# NQSMHS-SMD.net
KiCad netlist of a schematic drawn in EAGLE
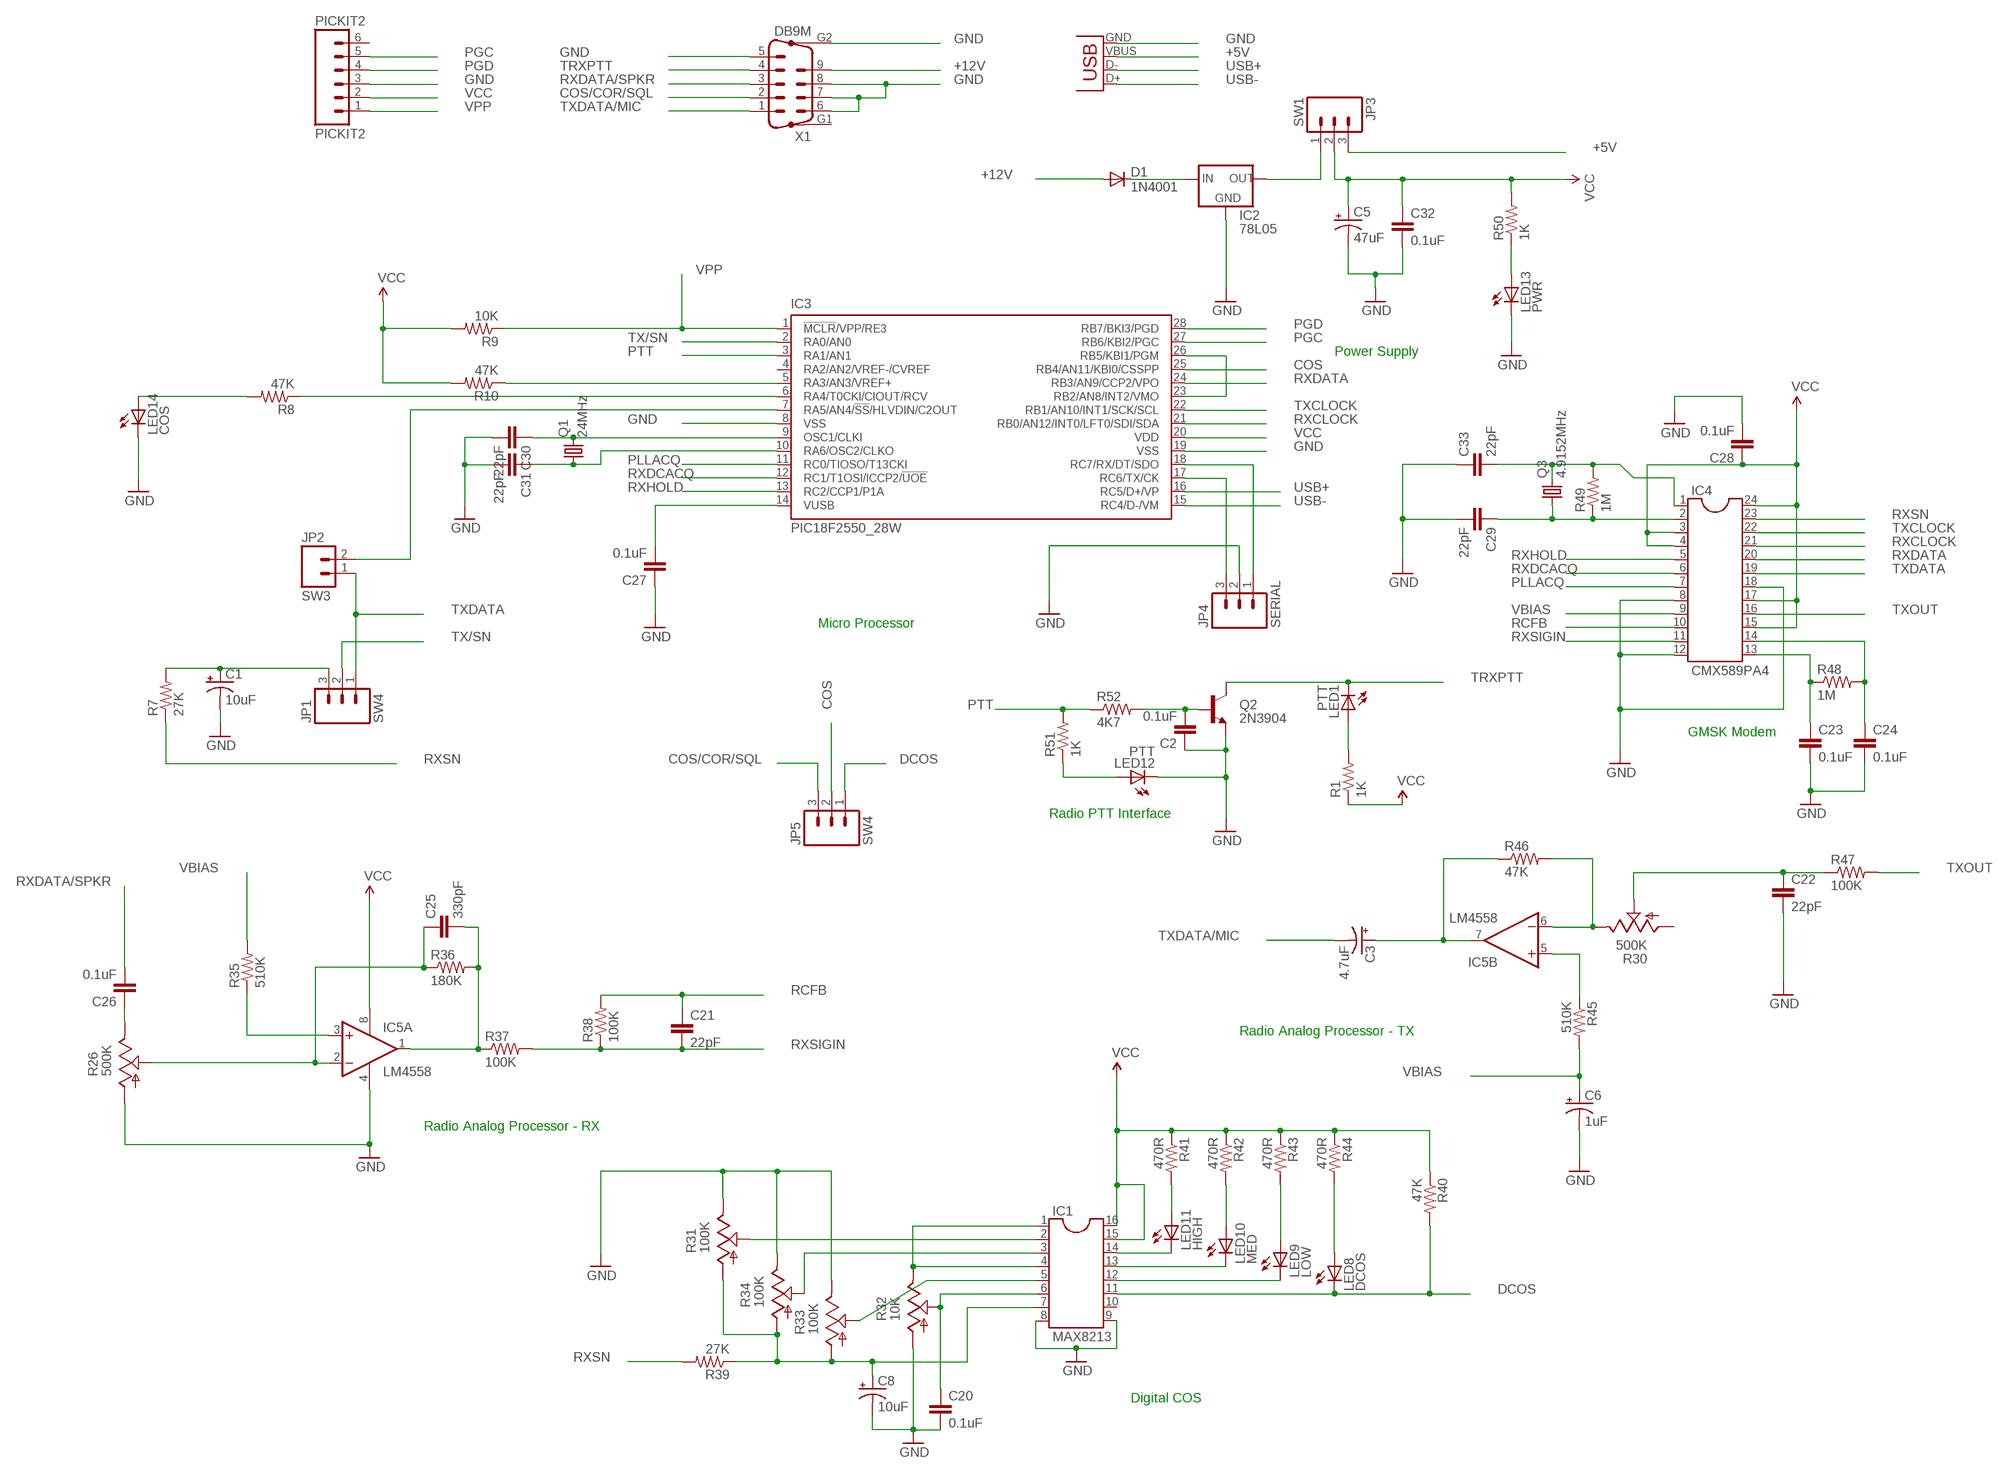
[diagram p0: schematic, sheet 1]

(export (version "E")
  (design (tool "Eeschema 10.0.6"))
  (components
    (comp (ref "C1")
      (value "10uF")
      (footprint "eagle-import:CPOL-RADIAL-100UF-25V")
      (libsource (lib "eagle-import") (part "CAP_POLPTH1"))
    )
    (comp (ref "C2")
      (value "0.1uF")
      (footprint "eagle-import:C0805")
      (libsource (lib "eagle-import") (part "C-EUC0805"))
    )
    (comp (ref "C3")
      (value "4.7uF")
      (footprint "eagle-import:CPOL-RADIAL-10UF-25V")
      (libsource (lib "eagle-import") (part "CAP_POLPTH2"))
    )
    (comp (ref "C5")
      (value "47uF")
      (footprint "eagle-import:CPOL-RADIAL-10UF-25V")
      (libsource (lib "eagle-import") (part "CAP_POLPTH2"))
    )
    (comp (ref "C6")
      (value "1uF")
      (footprint "eagle-import:CPOL-RADIAL-10UF-25V")
      (libsource (lib "eagle-import") (part "CAP_POLPTH2"))
    )
    (comp (ref "C8")
      (value "10uF")
      (footprint "eagle-import:CPOL-RADIAL-10UF-25V")
      (libsource (lib "eagle-import") (part "CAP_POLPTH2"))
    )
    (comp (ref "C20")
      (value "0.1uF")
      (footprint "eagle-import:C0805")
      (libsource (lib "eagle-import") (part "C-EUC0805"))
    )
    (comp (ref "C21")
      (value "22pF")
      (footprint "eagle-import:C0805")
      (libsource (lib "eagle-import") (part "C-EUC0805"))
    )
    (comp (ref "C22")
      (value "22pF")
      (footprint "eagle-import:C0805")
      (libsource (lib "eagle-import") (part "C-EUC0805"))
    )
    (comp (ref "C23")
      (value "0.1uF")
      (footprint "eagle-import:C0805")
      (libsource (lib "eagle-import") (part "C-EUC0805"))
    )
    (comp (ref "C24")
      (value "0.1uF")
      (footprint "eagle-import:C0805")
      (libsource (lib "eagle-import") (part "C-EUC0805"))
    )
    (comp (ref "C25")
      (value "330pF")
      (footprint "eagle-import:C0805")
      (libsource (lib "eagle-import") (part "C-EUC0805"))
    )
    (comp (ref "C26")
      (value "0.1uF")
      (footprint "eagle-import:C0805")
      (libsource (lib "eagle-import") (part "C-EUC0805"))
    )
    (comp (ref "C27")
      (value "0.1uF")
      (footprint "eagle-import:C0805")
      (libsource (lib "eagle-import") (part "C-EUC0805"))
    )
    (comp (ref "C28")
      (value "0.1uF")
      (footprint "eagle-import:C0805")
      (libsource (lib "eagle-import") (part "C-EUC0805"))
    )
    (comp (ref "C29")
      (value "22pF")
      (footprint "eagle-import:C0805")
      (libsource (lib "eagle-import") (part "C-EUC0805"))
    )
    (comp (ref "C30")
      (value "22pF")
      (footprint "eagle-import:C0805")
      (libsource (lib "eagle-import") (part "C-EUC0805"))
    )
    (comp (ref "C31")
      (value "22pF")
      (footprint "eagle-import:C0805")
      (libsource (lib "eagle-import") (part "C-EUC0805"))
    )
    (comp (ref "C32")
      (value "0.1uF")
      (footprint "eagle-import:C0805")
      (libsource (lib "eagle-import") (part "C-EUC0805"))
    )
    (comp (ref "C33")
      (value "22pF")
      (footprint "eagle-import:C0805")
      (libsource (lib "eagle-import") (part "C-EUC0805"))
    )
    (comp (ref "D1")
      (value "1N4001")
      (footprint "eagle-import:SOT23-3")
      (libsource (lib "eagle-import") (part "DIODESOT23"))
    )
    (comp (ref "IC1")
      (value "MAX8213")
      (footprint "eagle-import:DIL16")
      (libsource (lib "eagle-import") (part "DIL16"))
    )
    (comp (ref "IC2")
      (value "78L05")
      (footprint "eagle-import:78LXX")
      (libsource (lib "eagle-import") (part "78LXX"))
    )
    (comp (ref "IC3")
      (value "PIC18F2550_28W")
      (footprint "eagle-import:SO28W")
      (libsource (lib "eagle-import") (part "PIC18F2_28W550"))
    )
    (comp (ref "IC4")
      (value "CMX589PA4")
      (footprint "eagle-import:DIL24-6")
      (libsource (lib "eagle-import") (part "DIL24-6"))
    )
    (comp (ref "IC5")
      (value "LM4558")
      (footprint "eagle-import:SO08")
      (libsource (lib "eagle-import") (part "OPA2U344"))
    )
    (comp (ref "J1")
      (value "USBSMD")
      (footprint "eagle-import:USB-MINIB")
      (libsource (lib "eagle-import") (part "USBSMD"))
    )
    (comp (ref "JP1")
      (value "SW4")
      (footprint "eagle-import:1X03")
      (libsource (lib "eagle-import") (part "M03PTH"))
    )
    (comp (ref "JP2")
      (value "SW3")
      (footprint "eagle-import:1X02")
      (libsource (lib "eagle-import") (part "M02PTH"))
    )
    (comp (ref "JP3")
      (value "SW1")
      (footprint "eagle-import:1X03")
      (libsource (lib "eagle-import") (part "M03PTH"))
    )
    (comp (ref "JP4")
      (value "SERIAL")
      (footprint "eagle-import:1X03")
      (libsource (lib "eagle-import") (part "M03PTH"))
    )
    (comp (ref "JP5")
      (value "SW4")
      (footprint "eagle-import:1X03")
      (libsource (lib "eagle-import") (part "M03PTH"))
    )
    (comp (ref "LED1")
      (value "PTT")
      (footprint "eagle-import:CHIP-LED0805")
      (libsource (lib "eagle-import") (part "LEDCHIP-LED0805"))
    )
    (comp (ref "LED8")
      (value "DCOS")
      (footprint "eagle-import:CHIP-LED0805")
      (libsource (lib "eagle-import") (part "LEDCHIP-LED0805"))
    )
    (comp (ref "LED9")
      (value "LOW")
      (footprint "eagle-import:CHIP-LED0805")
      (libsource (lib "eagle-import") (part "LEDCHIP-LED0805"))
    )
    (comp (ref "LED10")
      (value "MED")
      (footprint "eagle-import:CHIP-LED0805")
      (libsource (lib "eagle-import") (part "LEDCHIP-LED0805"))
    )
    (comp (ref "LED11")
      (value "HIGH")
      (footprint "eagle-import:CHIP-LED0805")
      (libsource (lib "eagle-import") (part "LEDCHIP-LED0805"))
    )
    (comp (ref "LED12")
      (value "PTT")
      (footprint "eagle-import:CHIP-LED0805")
      (libsource (lib "eagle-import") (part "LEDCHIP-LED0805"))
    )
    (comp (ref "LED13")
      (value "PWR")
      (footprint "eagle-import:CHIP-LED0805")
      (libsource (lib "eagle-import") (part "LEDCHIP-LED0805"))
    )
    (comp (ref "LED14")
      (value "COS")
      (footprint "eagle-import:CHIP-LED0805")
      (libsource (lib "eagle-import") (part "LEDCHIP-LED0805"))
    )
    (comp (ref "PICKIT2")
      (value "PICKIT2")
      (footprint "eagle-import:1X06")
      (libsource (lib "eagle-import") (part "M06SIP"))
    )
    (comp (ref "Q1")
      (value "24MHz")
      (footprint "eagle-import:CRYSTAL-SMD-10.5X4.8-2PIN")
      (libsource (lib "eagle-import") (part "CRYSTAL10.5X4.8"))
    )
    (comp (ref "Q2")
      (value "2N3904")
      (footprint "eagle-import:SOT23")
      (libsource (lib "eagle-import") (part "TRANSISTOR_NPNSOT23"))
    )
    (comp (ref "Q3")
      (value "4.9152MHz")
      (footprint "eagle-import:CRYSTAL-SMD-10.5X4.8-2PIN")
      (libsource (lib "eagle-import") (part "CRYSTAL10.5X4.8"))
    )
    (comp (ref "R1")
      (value "1K")
      (footprint "eagle-import:R0805")
      (libsource (lib "eagle-import") (part "R-US_R0805"))
    )
    (comp (ref "R7")
      (value "27K")
      (footprint "eagle-import:R0805")
      (libsource (lib "eagle-import") (part "R-US_R0805"))
    )
    (comp (ref "R8")
      (value "47K")
      (footprint "eagle-import:R0805")
      (libsource (lib "eagle-import") (part "R-US_R0805"))
    )
    (comp (ref "R9")
      (value "10K")
      (footprint "eagle-import:R0805")
      (libsource (lib "eagle-import") (part "R-US_R0805"))
    )
    (comp (ref "R10")
      (value "47K")
      (footprint "eagle-import:R0805")
      (libsource (lib "eagle-import") (part "R-US_R0805"))
    )
    (comp (ref "R26")
      (value "500K")
      (footprint "eagle-import:CA6V")
      (libsource (lib "eagle-import") (part "TRIM_US-CA6V"))
    )
    (comp (ref "R30")
      (value "500K")
      (footprint "eagle-import:CA6V")
      (libsource (lib "eagle-import") (part "TRIM_US-CA6V"))
    )
    (comp (ref "R31")
      (value "100K")
      (footprint "eagle-import:CA6V")
      (libsource (lib "eagle-import") (part "TRIM_US-CA6V"))
    )
    (comp (ref "R32")
      (value "10K")
      (footprint "eagle-import:CA6V")
      (libsource (lib "eagle-import") (part "TRIM_US-CA6V"))
    )
    (comp (ref "R33")
      (value "100K")
      (footprint "eagle-import:CA6V")
      (libsource (lib "eagle-import") (part "TRIM_US-CA6V"))
    )
    (comp (ref "R34")
      (value "100K")
      (footprint "eagle-import:CA6V")
      (libsource (lib "eagle-import") (part "TRIM_US-CA6V"))
    )
    (comp (ref "R35")
      (value "510K")
      (footprint "eagle-import:R0805")
      (libsource (lib "eagle-import") (part "R-US_R0805"))
    )
    (comp (ref "R36")
      (value "180K")
      (footprint "eagle-import:R0805")
      (libsource (lib "eagle-import") (part "R-US_R0805"))
    )
    (comp (ref "R37")
      (value "100K")
      (footprint "eagle-import:R0805")
      (libsource (lib "eagle-import") (part "R-US_R0805"))
    )
    (comp (ref "R38")
      (value "100K")
      (footprint "eagle-import:R0805")
      (libsource (lib "eagle-import") (part "R-US_R0805"))
    )
    (comp (ref "R39")
      (value "27K")
      (footprint "eagle-import:R0805")
      (libsource (lib "eagle-import") (part "R-US_R0805"))
    )
    (comp (ref "R40")
      (value "47K")
      (footprint "eagle-import:R0805")
      (libsource (lib "eagle-import") (part "R-US_R0805"))
    )
    (comp (ref "R41")
      (value "470R")
      (footprint "eagle-import:R0805")
      (libsource (lib "eagle-import") (part "R-US_R0805"))
    )
    (comp (ref "R42")
      (value "470R")
      (footprint "eagle-import:R0805")
      (libsource (lib "eagle-import") (part "R-US_R0805"))
    )
    (comp (ref "R43")
      (value "470R")
      (footprint "eagle-import:R0805")
      (libsource (lib "eagle-import") (part "R-US_R0805"))
    )
    (comp (ref "R44")
      (value "470R")
      (footprint "eagle-import:R0805")
      (libsource (lib "eagle-import") (part "R-US_R0805"))
    )
    (comp (ref "R45")
      (value "510K")
      (footprint "eagle-import:R0805")
      (libsource (lib "eagle-import") (part "R-US_R0805"))
    )
    (comp (ref "R46")
      (value "47K")
      (footprint "eagle-import:R0805")
      (libsource (lib "eagle-import") (part "R-US_R0805"))
    )
    (comp (ref "R47")
      (value "100K")
      (footprint "eagle-import:R0805")
      (libsource (lib "eagle-import") (part "R-US_R0805"))
    )
    (comp (ref "R48")
      (value "1M")
      (footprint "eagle-import:R0805")
      (libsource (lib "eagle-import") (part "R-US_R0805"))
    )
    (comp (ref "R49")
      (value "1M")
      (footprint "eagle-import:R0805")
      (libsource (lib "eagle-import") (part "R-US_R0805"))
    )
    (comp (ref "R50")
      (value "1K")
      (footprint "eagle-import:R0805")
      (libsource (lib "eagle-import") (part "R-US_R0805"))
    )
    (comp (ref "R51")
      (value "1K")
      (footprint "eagle-import:R0805")
      (libsource (lib "eagle-import") (part "R-US_R0805"))
    )
    (comp (ref "R52")
      (value "4K7")
      (footprint "eagle-import:R0805")
      (libsource (lib "eagle-import") (part "R-US_R0805"))
    )
    (comp (ref "X1")
      (value "DB9M")
      (footprint "eagle-import:M09HP")
      (libsource (lib "eagle-import") (part "M09HP"))
    )
  )
  (nets
    (net (code "1") (name "/+5V") (class "Default")
      (node (ref "J1") (pin "VBUS") (pinfunction "VBUS_VBUS") (pintype "bidirectional"))
      (node (ref "JP3") (pin "3") (pinfunction "3_3") (pintype "passive"))
    )
    (net (code "2") (name "/+12V") (class "Default")
      (node (ref "D1") (pin "1") (pinfunction "A_1") (pintype "passive"))
      (node (ref "X1") (pin "9") (pinfunction "9_9") (pintype "passive"))
    )
    (net (code "3") (name "/COS") (class "Default")
      (node (ref "IC3") (pin "25") (pinfunction "RB4/AN11/KBI0/CSSPP_25") (pintype "bidirectional"))
      (node (ref "JP5") (pin "2") (pinfunction "2_2") (pintype "passive"))
    )
    (net (code "4") (name "/COS{slash}COR{slash}SQL") (class "Default")
      (node (ref "JP5") (pin "3") (pinfunction "3_3") (pintype "passive"))
      (node (ref "X1") (pin "2") (pinfunction "2_2") (pintype "passive"))
    )
    (net (code "5") (name "/DCOS") (class "Default")
      (node (ref "IC1") (pin "11") (pinfunction "11_11") (pintype "passive"))
      (node (ref "JP5") (pin "1") (pinfunction "1_1") (pintype "passive"))
      (node (ref "LED8") (pin "C") (pinfunction "C_C") (pintype "passive"))
      (node (ref "R40") (pin "2") (pinfunction "2_2") (pintype "passive"))
    )
    (net (code "6") (name "/PGC") (class "Default")
      (node (ref "IC3") (pin "27") (pinfunction "RB6/KBI2/PGC_27") (pintype "bidirectional"))
      (node (ref "PICKIT2") (pin "5") (pinfunction "5_5") (pintype "passive"))
    )
    (net (code "7") (name "/PGD") (class "Default")
      (node (ref "IC3") (pin "28") (pinfunction "RB7/BKI3/PGD_28") (pintype "bidirectional"))
      (node (ref "PICKIT2") (pin "4") (pinfunction "4_4") (pintype "passive"))
    )
    (net (code "8") (name "/PLLACQ") (class "Default")
      (node (ref "IC3") (pin "11") (pinfunction "RC0/TIOSO/T13CKI_11") (pintype "bidirectional"))
      (node (ref "IC4") (pin "7") (pinfunction "7_7") (pintype "passive"))
    )
    (net (code "9") (name "/PTT") (class "Default")
      (node (ref "IC3") (pin "3") (pinfunction "RA1/AN1_3") (pintype "bidirectional"))
      (node (ref "R51") (pin "2") (pinfunction "2_2") (pintype "passive"))
      (node (ref "R52") (pin "1") (pinfunction "1_1") (pintype "passive"))
    )
    (net (code "10") (name "/RCFB") (class "Default")
      (node (ref "C21") (pin "1") (pinfunction "1_1") (pintype "passive"))
      (node (ref "IC4") (pin "10") (pinfunction "10_10") (pintype "passive"))
      (node (ref "R38") (pin "2") (pinfunction "2_2") (pintype "passive"))
    )
    (net (code "11") (name "/RXCLOCK") (class "Default")
      (node (ref "IC3") (pin "21") (pinfunction "RB0/AN12/INT0/LFT0/SDI/SDA_21") (pintype "bidirectional"))
      (node (ref "IC4") (pin "21") (pinfunction "21_21") (pintype "passive"))
    )
    (net (code "12") (name "/RXDATA") (class "Default")
      (node (ref "IC3") (pin "24") (pinfunction "RB3/AN9/CCP2/VPO_24") (pintype "bidirectional"))
      (node (ref "IC4") (pin "20") (pinfunction "20_20") (pintype "passive"))
    )
    (net (code "13") (name "/RXDATA{slash}SPKR") (class "Default")
      (node (ref "C26") (pin "2") (pinfunction "2_2") (pintype "passive"))
      (node (ref "X1") (pin "3") (pinfunction "3_3") (pintype "passive"))
    )
    (net (code "14") (name "/RXDCACQ") (class "Default")
      (node (ref "IC3") (pin "12") (pinfunction "RC1/T1OSI/ICCP2/~{UOE}_12") (pintype "bidirectional"))
      (node (ref "IC4") (pin "6") (pinfunction "6_6") (pintype "passive"))
    )
    (net (code "15") (name "/RXHOLD") (class "Default")
      (node (ref "IC3") (pin "13") (pinfunction "RC2/CCP1/P1A_13") (pintype "bidirectional"))
      (node (ref "IC4") (pin "5") (pinfunction "5_5") (pintype "passive"))
    )
    (net (code "16") (name "/RXSIGIN") (class "Default")
      (node (ref "C21") (pin "2") (pinfunction "2_2") (pintype "passive"))
      (node (ref "IC4") (pin "11") (pinfunction "11_11") (pintype "passive"))
      (node (ref "R37") (pin "2") (pinfunction "2_2") (pintype "passive"))
      (node (ref "R38") (pin "1") (pinfunction "1_1") (pintype "passive"))
    )
    (net (code "17") (name "/RXSN") (class "Default")
      (node (ref "IC4") (pin "23") (pinfunction "23_23") (pintype "passive"))
      (node (ref "R39") (pin "2") (pinfunction "2_2") (pintype "passive"))
      (node (ref "R7") (pin "1") (pinfunction "1_1") (pintype "passive"))
    )
    (net (code "18") (name "/TRXPTT") (class "Default")
      (node (ref "LED1") (pin "C") (pinfunction "C_C") (pintype "passive"))
      (node (ref "Q2") (pin "3") (pinfunction "C_3") (pintype "passive"))
      (node (ref "X1") (pin "4") (pinfunction "4_4") (pintype "passive"))
    )
    (net (code "19") (name "/TXCLOCK") (class "Default")
      (node (ref "IC3") (pin "22") (pinfunction "RB1/AN10/INT1/SCK/SCL_22") (pintype "bidirectional"))
      (node (ref "IC4") (pin "22") (pinfunction "22_22") (pintype "passive"))
    )
    (net (code "20") (name "/TXDATA") (class "Default")
      (node (ref "IC4") (pin "19") (pinfunction "19_19") (pintype "passive"))
      (node (ref "JP1") (pin "1") (pinfunction "1_1") (pintype "passive"))
      (node (ref "JP2") (pin "1") (pinfunction "1_1") (pintype "passive"))
    )
    (net (code "21") (name "/TXDATA{slash}MIC") (class "Default")
      (node (ref "C3") (pin "2") (pinfunction "-_2") (pintype "passive"))
      (node (ref "X1") (pin "1") (pinfunction "1_1") (pintype "passive"))
    )
    (net (code "22") (name "/TXOUT") (class "Default")
      (node (ref "IC4") (pin "16") (pinfunction "16_16") (pintype "passive"))
      (node (ref "R47") (pin "2") (pinfunction "2_2") (pintype "passive"))
    )
    (net (code "23") (name "/TX{slash}SN") (class "Default")
      (node (ref "IC3") (pin "2") (pinfunction "RA0/AN0_2") (pintype "bidirectional"))
      (node (ref "JP1") (pin "2") (pinfunction "2_2") (pintype "passive"))
    )
    (net (code "24") (name "/USB+") (class "Default")
      (node (ref "IC3") (pin "16") (pinfunction "RC5/D+/VP_16") (pintype "bidirectional"))
      (node (ref "J1") (pin "D-") (pinfunction "D-_D-") (pintype "bidirectional"))
    )
    (net (code "25") (name "/USB-") (class "Default")
      (node (ref "IC3") (pin "15") (pinfunction "RC4/D-/VM_15") (pintype "bidirectional"))
      (node (ref "J1") (pin "D+") (pinfunction "D+_D+") (pintype "bidirectional"))
    )
    (net (code "26") (name "/VBIAS") (class "Default")
      (node (ref "C6") (pin "1") (pinfunction "+_1") (pintype "passive"))
      (node (ref "IC4") (pin "9") (pinfunction "9_9") (pintype "passive"))
      (node (ref "R35") (pin "2") (pinfunction "2_2") (pintype "passive"))
      (node (ref "R45") (pin "2") (pinfunction "2_2") (pintype "passive"))
    )
    (net (code "27") (name "/VPP") (class "Default")
      (node (ref "IC3") (pin "1") (pinfunction "~{MCLR}/VPP/RE3_1") (pintype "input"))
      (node (ref "PICKIT2") (pin "1") (pinfunction "1_1") (pintype "passive"))
      (node (ref "R9") (pin "1") (pinfunction "1_1") (pintype "passive"))
    )
    (net (code "28") (name "GND") (class "Default")
      (node (ref "C1") (pin "2") (pinfunction "-_2") (pintype "passive"))
      (node (ref "C2") (pin "1") (pinfunction "1_1") (pintype "passive"))
      (node (ref "C20") (pin "2") (pinfunction "2_2") (pintype "passive"))
      (node (ref "C22") (pin "2") (pinfunction "2_2") (pintype "passive"))
      (node (ref "C23") (pin "2") (pinfunction "2_2") (pintype "passive"))
      (node (ref "C24") (pin "2") (pinfunction "2_2") (pintype "passive"))
      (node (ref "C27") (pin "1") (pinfunction "1_1") (pintype "passive"))
      (node (ref "C28") (pin "2") (pinfunction "2_2") (pintype "passive"))
      (node (ref "C29") (pin "2") (pinfunction "2_2") (pintype "passive"))
      (node (ref "C30") (pin "2") (pinfunction "2_2") (pintype "passive"))
      (node (ref "C31") (pin "2") (pinfunction "2_2") (pintype "passive"))
      (node (ref "C32") (pin "2") (pinfunction "2_2") (pintype "passive"))
      (node (ref "C33") (pin "1") (pinfunction "1_1") (pintype "passive"))
      (node (ref "C5") (pin "2") (pinfunction "-_2") (pintype "passive"))
      (node (ref "C6") (pin "2") (pinfunction "-_2") (pintype "passive"))
      (node (ref "C8") (pin "2") (pinfunction "-_2") (pintype "passive"))
      (node (ref "IC1") (pin "8") (pinfunction "8_8") (pintype "passive"))
      (node (ref "IC1") (pin "9") (pinfunction "9_9") (pintype "passive"))
      (node (ref "IC2") (pin "GND") (pinfunction "GND_GND") (pintype "input"))
      (node (ref "IC3") (pin "19") (pinfunction "VSS_19") (pintype "power_in"))
      (node (ref "IC3") (pin "8") (pinfunction "VSS_8") (pintype "power_in"))
      (node (ref "IC4") (pin "12") (pinfunction "12_12") (pintype "passive"))
      (node (ref "IC4") (pin "18") (pinfunction "18_18") (pintype "passive"))
      (node (ref "IC4") (pin "8") (pinfunction "8_8") (pintype "passive"))
      (node (ref "IC5") (pin "4") (pinfunction "V-_4") (pintype "power_in"))
      (node (ref "J1") (pin "GND") (pinfunction "GND_GND") (pintype "bidirectional"))
      (node (ref "JP4") (pin "2") (pinfunction "2_2") (pintype "passive"))
      (node (ref "LED12") (pin "C") (pinfunction "C_C") (pintype "passive"))
      (node (ref "LED13") (pin "C") (pinfunction "C_C") (pintype "passive"))
      (node (ref "LED14") (pin "C") (pinfunction "C_C") (pintype "passive"))
      (node (ref "PICKIT2") (pin "3") (pinfunction "3_3") (pintype "passive"))
      (node (ref "Q2") (pin "2") (pinfunction "E_2") (pintype "passive"))
      (node (ref "R26") (pin "A") (pinfunction "A_A") (pintype "passive"))
      (node (ref "R31") (pin "E") (pinfunction "E_E") (pintype "passive"))
      (node (ref "R32") (pin "A") (pinfunction "A_A") (pintype "passive"))
      (node (ref "R33") (pin "E") (pinfunction "E_E") (pintype "passive"))
      (node (ref "R34") (pin "E") (pinfunction "E_E") (pintype "passive"))
      (node (ref "X1") (pin "5") (pinfunction "5_5") (pintype "passive"))
      (node (ref "X1") (pin "6") (pinfunction "6_6") (pintype "passive"))
      (node (ref "X1") (pin "7") (pinfunction "7_7") (pintype "passive"))
      (node (ref "X1") (pin "8") (pinfunction "8_8") (pintype "passive"))
      (node (ref "X1") (pin "G2") (pinfunction "G2_G2") (pintype "passive"))
    )
    (net (code "29") (name "Net-(C1-+)") (class "Default")
      (node (ref "C1") (pin "1") (pinfunction "+_1") (pintype "passive"))
      (node (ref "JP1") (pin "3") (pinfunction "3_3") (pintype "passive"))
      (node (ref "R7") (pin "2") (pinfunction "2_2") (pintype "passive"))
    )
    (net (code "30") (name "Net-(C3-+)") (class "Default")
      (node (ref "C3") (pin "1") (pinfunction "+_1") (pintype "passive"))
      (node (ref "IC5") (pin "7") (pinfunction "OUT_7") (pintype "output"))
      (node (ref "R46") (pin "1") (pinfunction "1_1") (pintype "passive"))
    )
    (net (code "31") (name "Net-(C8-+)") (class "Default")
      (node (ref "C8") (pin "1") (pinfunction "+_1") (pintype "passive"))
      (node (ref "IC1") (pin "7") (pinfunction "7_7") (pintype "passive"))
      (node (ref "R31") (pin "A") (pinfunction "A_A") (pintype "passive"))
      (node (ref "R33") (pin "A") (pinfunction "A_A") (pintype "passive"))
      (node (ref "R34") (pin "A") (pinfunction "A_A") (pintype "passive"))
      (node (ref "R39") (pin "1") (pinfunction "1_1") (pintype "passive"))
    )
    (net (code "32") (name "Net-(C20-Pad1)") (class "Default")
      (node (ref "C20") (pin "1") (pinfunction "1_1") (pintype "passive"))
      (node (ref "IC1") (pin "6") (pinfunction "6_6") (pintype "passive"))
      (node (ref "R32") (pin "S") (pinfunction "S_S") (pintype "passive"))
    )
    (net (code "33") (name "Net-(C22-Pad1)") (class "Default")
      (node (ref "C22") (pin "1") (pinfunction "1_1") (pintype "passive"))
      (node (ref "R30") (pin "S") (pinfunction "S_S") (pintype "passive"))
      (node (ref "R47") (pin "1") (pinfunction "1_1") (pintype "passive"))
    )
    (net (code "34") (name "Net-(C23-Pad1)") (class "Default")
      (node (ref "C23") (pin "1") (pinfunction "1_1") (pintype "passive"))
      (node (ref "IC4") (pin "13") (pinfunction "13_13") (pintype "passive"))
      (node (ref "R48") (pin "1") (pinfunction "1_1") (pintype "passive"))
    )
    (net (code "35") (name "Net-(C24-Pad1)") (class "Default")
      (node (ref "C24") (pin "1") (pinfunction "1_1") (pintype "passive"))
      (node (ref "IC4") (pin "14") (pinfunction "14_14") (pintype "passive"))
      (node (ref "R48") (pin "2") (pinfunction "2_2") (pintype "passive"))
    )
    (net (code "36") (name "Net-(C26-Pad1)") (class "Default")
      (node (ref "C26") (pin "1") (pinfunction "1_1") (pintype "passive"))
      (node (ref "R26") (pin "E") (pinfunction "E_E") (pintype "passive"))
    )
    (net (code "37") (name "Net-(D1-C)") (class "Default")
      (node (ref "D1") (pin "3") (pinfunction "C_3") (pintype "passive"))
      (node (ref "IC2") (pin "IN") (pinfunction "IN_IN") (pintype "input"))
    )
    (net (code "38") (name "Net-(IC1-Pad1)") (class "Default")
      (node (ref "IC1") (pin "1") (pinfunction "1_1") (pintype "passive"))
      (node (ref "IC1") (pin "4") (pinfunction "4_4") (pintype "passive"))
      (node (ref "R32") (pin "E") (pinfunction "E_E") (pintype "passive"))
    )
    (net (code "39") (name "Net-(IC1-Pad2)") (class "Default")
      (node (ref "IC1") (pin "2") (pinfunction "2_2") (pintype "passive"))
      (node (ref "R31") (pin "S") (pinfunction "S_S") (pintype "passive"))
    )
    (net (code "40") (name "Net-(IC1-Pad3)") (class "Default")
      (node (ref "IC1") (pin "3") (pinfunction "3_3") (pintype "passive"))
      (node (ref "R34") (pin "S") (pinfunction "S_S") (pintype "passive"))
    )
    (net (code "41") (name "Net-(IC1-Pad5)") (class "Default")
      (node (ref "IC1") (pin "5") (pinfunction "5_5") (pintype "passive"))
      (node (ref "R33") (pin "S") (pinfunction "S_S") (pintype "passive"))
    )
    (net (code "42") (name "Net-(IC1-Pad12)") (class "Default")
      (node (ref "IC1") (pin "12") (pinfunction "12_12") (pintype "passive"))
      (node (ref "LED9") (pin "C") (pinfunction "C_C") (pintype "passive"))
    )
    (net (code "43") (name "Net-(IC1-Pad13)") (class "Default")
      (node (ref "IC1") (pin "13") (pinfunction "13_13") (pintype "passive"))
      (node (ref "LED10") (pin "C") (pinfunction "C_C") (pintype "passive"))
    )
    (net (code "44") (name "Net-(IC1-Pad14)") (class "Default")
      (node (ref "IC1") (pin "14") (pinfunction "14_14") (pintype "passive"))
      (node (ref "LED11") (pin "C") (pinfunction "C_C") (pintype "passive"))
    )
    (net (code "45") (name "Net-(IC2-PadOUT)") (class "Default")
      (node (ref "IC2") (pin "OUT") (pinfunction "OUT_OUT") (pintype "passive"))
      (node (ref "JP3") (pin "1") (pinfunction "1_1") (pintype "passive"))
    )
    (net (code "46") (name "Net-(IC3-OSC1{slash}CLKI)") (class "Default")
      (node (ref "C30") (pin "1") (pinfunction "1_1") (pintype "passive"))
      (node (ref "IC3") (pin "9") (pinfunction "OSC1/CLKI_9") (pintype "input"))
      (node (ref "Q1") (pin "P$2") (pinfunction "2_P$2") (pintype "passive"))
    )
    (net (code "47") (name "Net-(IC3-RA3{slash}AN3{slash}VREF+)") (class "Default")
      (node (ref "IC3") (pin "5") (pinfunction "RA3/AN3/VREF+_5") (pintype "bidirectional"))
      (node (ref "R10") (pin "1") (pinfunction "1_1") (pintype "passive"))
    )
    (net (code "48") (name "Net-(IC3-RA4{slash}T0CKI{slash}CIOUT{slash}RCV)") (class "Default")
      (node (ref "IC3") (pin "6") (pinfunction "RA4/T0CKI/CIOUT/RCV_6") (pintype "bidirectional"))
      (node (ref "R8") (pin "1") (pinfunction "1_1") (pintype "passive"))
    )
    (net (code "49") (name "Net-(IC3-RA5{slash}AN4{slash}~{SS}{slash}HLVDIN{slash}C2OUT)") (class "Default")
      (node (ref "IC3") (pin "7") (pinfunction "RA5/AN4/~{SS}/HLVDIN/C2OUT_7") (pintype "bidirectional"))
      (node (ref "JP2") (pin "2") (pinfunction "2_2") (pintype "passive"))
    )
    (net (code "50") (name "Net-(IC3-RA6{slash}OSC2{slash}CLKO)") (class "Default")
      (node (ref "C31") (pin "1") (pinfunction "1_1") (pintype "passive"))
      (node (ref "IC3") (pin "10") (pinfunction "RA6/OSC2/CLKO_10") (pintype "output"))
      (node (ref "Q1") (pin "P$1") (pinfunction "1_P$1") (pintype "passive"))
    )
    (net (code "51") (name "Net-(IC3-RB2{slash}AN8{slash}INT2{slash}VMO)") (class "Default")
      (node (ref "IC3") (pin "23") (pinfunction "RB2/AN8/INT2/VMO_23") (pintype "bidirectional"))
      (node (ref "IC3") (pin "26") (pinfunction "RB5/KBI1/PGM_26") (pintype "bidirectional"))
    )
    (net (code "52") (name "Net-(IC3-RC6{slash}TX{slash}CK)") (class "Default")
      (node (ref "IC3") (pin "17") (pinfunction "RC6/TX/CK_17") (pintype "bidirectional"))
      (node (ref "JP4") (pin "3") (pinfunction "3_3") (pintype "passive"))
    )
    (net (code "53") (name "Net-(IC3-RC7{slash}RX{slash}DT{slash}SDO)") (class "Default")
      (node (ref "IC3") (pin "18") (pinfunction "RC7/RX/DT/SDO_18") (pintype "bidirectional"))
      (node (ref "JP4") (pin "1") (pinfunction "1_1") (pintype "passive"))
    )
    (net (code "54") (name "Net-(IC3-VUSB)") (class "Default")
      (node (ref "C27") (pin "2") (pinfunction "2_2") (pintype "passive"))
      (node (ref "IC3") (pin "14") (pinfunction "VUSB_14") (pintype "bidirectional"))
    )
    (net (code "55") (name "Net-(IC5A-+IN)") (class "Default")
      (node (ref "IC5") (pin "3") (pinfunction "+IN_3") (pintype "input"))
      (node (ref "R35") (pin "1") (pinfunction "1_1") (pintype "passive"))
    )
    (net (code "56") (name "Net-(IC5A--IN)") (class "Default")
      (node (ref "C25") (pin "1") (pinfunction "1_1") (pintype "passive"))
      (node (ref "IC5") (pin "2") (pinfunction "-IN_2") (pintype "input"))
      (node (ref "R26") (pin "S") (pinfunction "S_S") (pintype "passive"))
      (node (ref "R36") (pin "1") (pinfunction "1_1") (pintype "passive"))
    )
    (net (code "57") (name "Net-(IC5A-OUT)") (class "Default")
      (node (ref "C25") (pin "2") (pinfunction "2_2") (pintype "passive"))
      (node (ref "IC5") (pin "1") (pinfunction "OUT_1") (pintype "output"))
      (node (ref "R36") (pin "2") (pinfunction "2_2") (pintype "passive"))
      (node (ref "R37") (pin "1") (pinfunction "1_1") (pintype "passive"))
    )
    (net (code "58") (name "Net-(IC5B-+IN)") (class "Default")
      (node (ref "IC5") (pin "5") (pinfunction "+IN_5") (pintype "input"))
      (node (ref "R45") (pin "1") (pinfunction "1_1") (pintype "passive"))
    )
    (net (code "59") (name "Net-(IC5B--IN)") (class "Default")
      (node (ref "IC5") (pin "6") (pinfunction "-IN_6") (pintype "input"))
      (node (ref "R30") (pin "E") (pinfunction "E_E") (pintype "passive"))
      (node (ref "R46") (pin "2") (pinfunction "2_2") (pintype "passive"))
    )
    (net (code "60") (name "Net-(LED1-PadA)") (class "Default")
      (node (ref "LED1") (pin "A") (pinfunction "A_A") (pintype "passive"))
      (node (ref "R1") (pin "2") (pinfunction "2_2") (pintype "passive"))
    )
    (net (code "61") (name "Net-(LED8-PadA)") (class "Default")
      (node (ref "LED8") (pin "A") (pinfunction "A_A") (pintype "passive"))
      (node (ref "R44") (pin "2") (pinfunction "2_2") (pintype "passive"))
    )
    (net (code "62") (name "Net-(LED9-PadA)") (class "Default")
      (node (ref "LED9") (pin "A") (pinfunction "A_A") (pintype "passive"))
      (node (ref "R43") (pin "2") (pinfunction "2_2") (pintype "passive"))
    )
    (net (code "63") (name "Net-(LED10-PadA)") (class "Default")
      (node (ref "LED10") (pin "A") (pinfunction "A_A") (pintype "passive"))
      (node (ref "R42") (pin "2") (pinfunction "2_2") (pintype "passive"))
    )
    (net (code "64") (name "Net-(LED11-PadA)") (class "Default")
      (node (ref "LED11") (pin "A") (pinfunction "A_A") (pintype "passive"))
      (node (ref "R41") (pin "2") (pinfunction "2_2") (pintype "passive"))
    )
    (net (code "65") (name "Net-(LED12-PadA)") (class "Default")
      (node (ref "LED12") (pin "A") (pinfunction "A_A") (pintype "passive"))
      (node (ref "R51") (pin "1") (pinfunction "1_1") (pintype "passive"))
    )
    (net (code "66") (name "Net-(LED13-PadA)") (class "Default")
      (node (ref "LED13") (pin "A") (pinfunction "A_A") (pintype "passive"))
      (node (ref "R50") (pin "1") (pinfunction "1_1") (pintype "passive"))
    )
    (net (code "67") (name "Net-(LED14-PadA)") (class "Default")
      (node (ref "LED14") (pin "A") (pinfunction "A_A") (pintype "passive"))
      (node (ref "R8") (pin "2") (pinfunction "2_2") (pintype "passive"))
    )
    (net (code "68") (name "Net-(Q2-B)") (class "Default")
      (node (ref "C2") (pin "2") (pinfunction "2_2") (pintype "passive"))
      (node (ref "Q2") (pin "1") (pinfunction "B_1") (pintype "passive"))
      (node (ref "R52") (pin "2") (pinfunction "2_2") (pintype "passive"))
    )
    (net (code "69") (name "Net-(Q3-1)") (class "Default")
      (node (ref "C29") (pin "1") (pinfunction "1_1") (pintype "passive"))
      (node (ref "IC4") (pin "2") (pinfunction "2_2") (pintype "passive"))
      (node (ref "Q3") (pin "P$1") (pinfunction "1_P$1") (pintype "passive"))
      (node (ref "R49") (pin "1") (pinfunction "1_1") (pintype "passive"))
    )
    (net (code "70") (name "Net-(Q3-2)") (class "Default")
      (node (ref "C33") (pin "2") (pinfunction "2_2") (pintype "passive"))
      (node (ref "IC4") (pin "1") (pinfunction "1_1") (pintype "passive"))
      (node (ref "Q3") (pin "P$2") (pinfunction "2_P$2") (pintype "passive"))
      (node (ref "R49") (pin "2") (pinfunction "2_2") (pintype "passive"))
    )
    (net (code "71") (name "VCC") (class "Default")
      (node (ref "C28") (pin "1") (pinfunction "1_1") (pintype "passive"))
      (node (ref "C32") (pin "1") (pinfunction "1_1") (pintype "passive"))
      (node (ref "C5") (pin "1") (pinfunction "+_1") (pintype "passive"))
      (node (ref "IC1") (pin "15") (pinfunction "15_15") (pintype "passive"))
      (node (ref "IC1") (pin "16") (pinfunction "16_16") (pintype "passive"))
      (node (ref "IC3") (pin "20") (pinfunction "VDD_20") (pintype "power_in"))
      (node (ref "IC4") (pin "15") (pinfunction "15_15") (pintype "passive"))
      (node (ref "IC4") (pin "17") (pinfunction "17_17") (pintype "passive"))
      (node (ref "IC4") (pin "24") (pinfunction "24_24") (pintype "passive"))
      (node (ref "IC4") (pin "3") (pinfunction "3_3") (pintype "passive"))
      (node (ref "IC4") (pin "4") (pinfunction "4_4") (pintype "passive"))
      (node (ref "IC5") (pin "8") (pinfunction "V+_8") (pintype "power_in"))
      (node (ref "JP3") (pin "2") (pinfunction "2_2") (pintype "passive"))
      (node (ref "PICKIT2") (pin "2") (pinfunction "2_2") (pintype "passive"))
      (node (ref "R1") (pin "1") (pinfunction "1_1") (pintype "passive"))
      (node (ref "R10") (pin "2") (pinfunction "2_2") (pintype "passive"))
      (node (ref "R40") (pin "1") (pinfunction "1_1") (pintype "passive"))
      (node (ref "R41") (pin "1") (pinfunction "1_1") (pintype "passive"))
      (node (ref "R42") (pin "1") (pinfunction "1_1") (pintype "passive"))
      (node (ref "R43") (pin "1") (pinfunction "1_1") (pintype "passive"))
      (node (ref "R44") (pin "1") (pinfunction "1_1") (pintype "passive"))
      (node (ref "R50") (pin "2") (pinfunction "2_2") (pintype "passive"))
      (node (ref "R9") (pin "2") (pinfunction "2_2") (pintype "passive"))
    )
    (net (code "72") (name "unconnected-(IC1-Pad10)") (class "Default")
      (node (ref "IC1") (pin "10") (pinfunction "10_10") (pintype "passive"))
    )
    (net (code "73") (name "unconnected-(IC3-RA2{slash}AN2{slash}VREF-{slash}CVREF-Pad4)") (class "Default")
      (node (ref "IC3") (pin "4") (pinfunction "RA2/AN2/VREF-/CVREF_4") (pintype "bidirectional"))
    )
    (net (code "74") (name "unconnected-(PICKIT2-Pad6)") (class "Default")
      (node (ref "PICKIT2") (pin "6") (pinfunction "6_6") (pintype "passive"))
    )
    (net (code "75") (name "unconnected-(R30-PadA)") (class "Default")
      (node (ref "R30") (pin "A") (pinfunction "A_A") (pintype "passive"))
    )
    (net (code "76") (name "unconnected-(X1-PadG1)") (class "Default")
      (node (ref "X1") (pin "G1") (pinfunction "G1_G1") (pintype "passive"))
    )
  )
)
